# PCB-AC2b.net
KiCad netlist of a schematic drawn in EAGLE
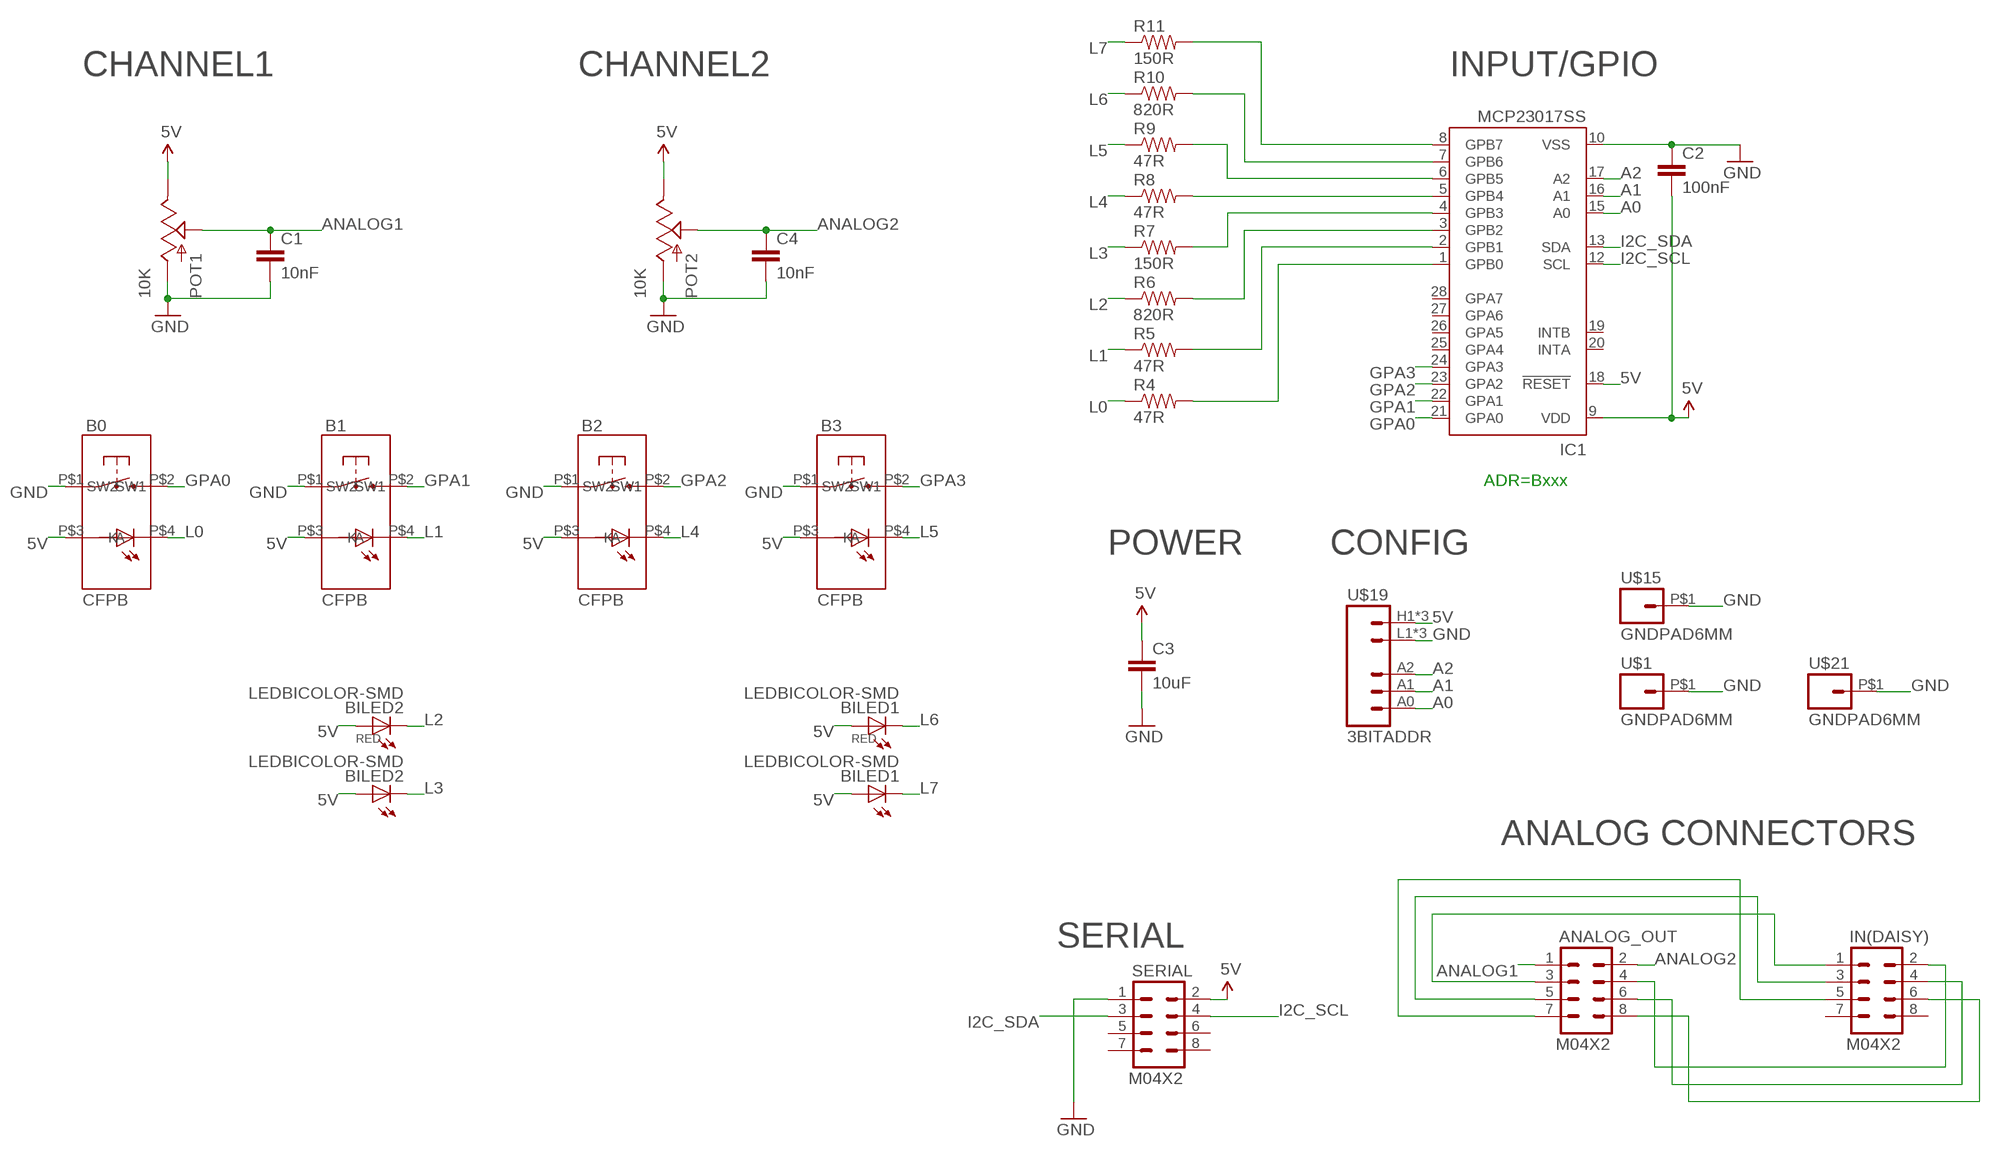
[diagram p0: schematic, sheet 1]

(export (version "E")
  (design (tool "Eeschema 10.0.6"))
  (components
    (comp (ref "ANALOG_OUT")
      (value "M04X2")
      (footprint "eagle-import:2X4")
      (libsource (lib "eagle-import") (part "M04X2"))
    )
    (comp (ref "B0")
      (value "CFPB")
      (footprint "eagle-import:CFPB-6_9MM")
      (libsource (lib "eagle-import") (part "CFPB"))
    )
    (comp (ref "B1")
      (value "CFPB")
      (footprint "eagle-import:CFPB-6_9MM")
      (libsource (lib "eagle-import") (part "CFPB"))
    )
    (comp (ref "B2")
      (value "CFPB")
      (footprint "eagle-import:CFPB-6_9MM")
      (libsource (lib "eagle-import") (part "CFPB"))
    )
    (comp (ref "B3")
      (value "CFPB")
      (footprint "eagle-import:CFPB-6_9MM")
      (libsource (lib "eagle-import") (part "CFPB"))
    )
    (comp (ref "BILED1")
      (value "LEDBICOLOR-SMD")
      (footprint "eagle-import:LEDBICOLOR-SMD")
      (libsource (lib "eagle-import") (part "LEDBICOLOR-SMD"))
    )
    (comp (ref "BILED2")
      (value "LEDBICOLOR-SMD")
      (footprint "eagle-import:LEDBICOLOR-SMD")
      (libsource (lib "eagle-import") (part "LEDBICOLOR-SMD"))
    )
    (comp (ref "C1")
      (value "10nF")
      (footprint "eagle-import:0603-CAP")
      (libsource (lib "eagle-import") (part "CAP0603-CAP"))
    )
    (comp (ref "C2")
      (value "100nF")
      (footprint "eagle-import:0603-CAP")
      (libsource (lib "eagle-import") (part "CAP0603-CAP"))
    )
    (comp (ref "C3")
      (value "10uF")
      (footprint "eagle-import:0805")
      (libsource (lib "eagle-import") (part "CAP0805"))
    )
    (comp (ref "C4")
      (value "10nF")
      (footprint "eagle-import:0603-CAP")
      (libsource (lib "eagle-import") (part "CAP0603-CAP"))
    )
    (comp (ref "IC1")
      (value "MCP23017SS")
      (footprint "eagle-import:SSOP28")
      (fields
        (field (name "MF") "MICROCHIP")
        (field (name "MPN") "MCP23017-E/SS")
        (field (name "MPN_1") "MCP23017-E/SS")
        (field (name "OC_FARNELL") "1467674")
        (field (name "OC_NEWARK") "31K2960")
      )
      (libsource (lib "eagle-import") (part "MCP23017SS"))
    )
    (comp (ref "IN(DAISY)")
      (value "M04X2")
      (footprint "eagle-import:2X4")
      (libsource (lib "eagle-import") (part "M04X2"))
    )
    (comp (ref "POT1")
      (value "10K")
      (footprint "eagle-import:ALPS_POT")
      (libsource (lib "eagle-import") (part "POT"))
    )
    (comp (ref "POT2")
      (value "10K")
      (footprint "eagle-import:ALPS_POT")
      (libsource (lib "eagle-import") (part "POT"))
    )
    (comp (ref "R4")
      (value "47R")
      (footprint "eagle-import:0603-RES")
      (libsource (lib "eagle-import") (part "RESISTOR0603-RES"))
    )
    (comp (ref "R5")
      (value "47R")
      (footprint "eagle-import:0603-RES")
      (libsource (lib "eagle-import") (part "RESISTOR0603-RES"))
    )
    (comp (ref "R6")
      (value "820R")
      (footprint "eagle-import:0603-RES")
      (libsource (lib "eagle-import") (part "RESISTOR0603-RES"))
    )
    (comp (ref "R7")
      (value "150R")
      (footprint "eagle-import:0603-RES")
      (libsource (lib "eagle-import") (part "RESISTOR0603-RES"))
    )
    (comp (ref "R8")
      (value "47R")
      (footprint "eagle-import:0603-RES")
      (libsource (lib "eagle-import") (part "RESISTOR0603-RES"))
    )
    (comp (ref "R9")
      (value "47R")
      (footprint "eagle-import:0603-RES")
      (libsource (lib "eagle-import") (part "RESISTOR0603-RES"))
    )
    (comp (ref "R10")
      (value "820R")
      (footprint "eagle-import:0603-RES")
      (libsource (lib "eagle-import") (part "RESISTOR0603-RES"))
    )
    (comp (ref "R11")
      (value "150R")
      (footprint "eagle-import:0603-RES")
      (libsource (lib "eagle-import") (part "RESISTOR0603-RES"))
    )
    (comp (ref "SERIAL")
      (value "M04X2")
      (footprint "eagle-import:2X4")
      (libsource (lib "eagle-import") (part "M04X2"))
    )
    (comp (ref "U$1")
      (value "GNDPAD6MM")
      (footprint "eagle-import:3.2MMPAD6MM")
      (libsource (lib "eagle-import") (part "GNDPAD6MM"))
    )
    (comp (ref "U$15")
      (value "GNDPAD6MM")
      (footprint "eagle-import:3.2MMPAD6MM")
      (libsource (lib "eagle-import") (part "GNDPAD6MM"))
    )
    (comp (ref "U$19")
      (value "3BITADDR")
      (footprint "eagle-import:3BITADDR")
      (libsource (lib "eagle-import") (part "3BITADDR"))
    )
    (comp (ref "U$21")
      (value "GNDPAD6MM")
      (footprint "eagle-import:3.2MMPAD6MM")
      (libsource (lib "eagle-import") (part "GNDPAD6MM"))
    )
  )
  (nets
    (net (code "1") (name "5V") (class "Default")
      (node (ref "B0") (pin "P$3") (pinfunction "A_P$3") (pintype "bidirectional"))
      (node (ref "B1") (pin "P$3") (pinfunction "A_P$3") (pintype "bidirectional"))
      (node (ref "B2") (pin "P$3") (pinfunction "A_P$3") (pintype "bidirectional"))
      (node (ref "B3") (pin "P$3") (pinfunction "A_P$3") (pintype "bidirectional"))
      (node (ref "BILED1") (pin "P$1") (pinfunction "A_P$1") (pintype "passive"))
      (node (ref "BILED1") (pin "P$3") (pinfunction "A1_P$3") (pintype "passive"))
      (node (ref "BILED2") (pin "P$1") (pinfunction "A_P$1") (pintype "passive"))
      (node (ref "BILED2") (pin "P$3") (pinfunction "A1_P$3") (pintype "passive"))
      (node (ref "C2") (pin "2") (pinfunction "2_2") (pintype "passive"))
      (node (ref "C3") (pin "1") (pinfunction "1_1") (pintype "passive"))
      (node (ref "IC1") (pin "18") (pinfunction "~{RESET}_18") (pintype "input"))
      (node (ref "IC1") (pin "9") (pinfunction "VDD_9") (pintype "power_in"))
      (node (ref "POT1") (pin "P$1") (pinfunction "E_P$1") (pintype "passive"))
      (node (ref "POT2") (pin "P$1") (pinfunction "E_P$1") (pintype "passive"))
      (node (ref "SERIAL") (pin "2") (pinfunction "2_2") (pintype "passive"))
      (node (ref "U$19") (pin "H1") (pinfunction "VCC_H1") (pintype "passive"))
      (node (ref "U$19") (pin "H2") (pinfunction "VCC_H2") (pintype "passive"))
      (node (ref "U$19") (pin "H3") (pinfunction "VCC_H3") (pintype "passive"))
    )
    (net (code "2") (name "A0") (class "Default")
      (node (ref "IC1") (pin "15") (pinfunction "A0_15") (pintype "input"))
      (node (ref "U$19") (pin "A0") (pinfunction "A0_A0") (pintype "passive"))
    )
    (net (code "3") (name "A1") (class "Default")
      (node (ref "IC1") (pin "16") (pinfunction "A1_16") (pintype "input"))
      (node (ref "U$19") (pin "A1") (pinfunction "A1_A1") (pintype "passive"))
    )
    (net (code "4") (name "A2") (class "Default")
      (node (ref "IC1") (pin "17") (pinfunction "A2_17") (pintype "input"))
      (node (ref "U$19") (pin "A2") (pinfunction "A2_A2") (pintype "passive"))
    )
    (net (code "5") (name "ANALOG1") (class "Default")
      (node (ref "ANALOG_OUT") (pin "1") (pinfunction "1_1") (pintype "passive"))
      (node (ref "C1") (pin "1") (pinfunction "1_1") (pintype "passive"))
      (node (ref "POT1") (pin "P$2") (pinfunction "S_P$2") (pintype "passive"))
    )
    (net (code "6") (name "ANALOG2") (class "Default")
      (node (ref "ANALOG_OUT") (pin "2") (pinfunction "2_2") (pintype "passive"))
      (node (ref "C4") (pin "1") (pinfunction "1_1") (pintype "passive"))
      (node (ref "POT2") (pin "P$2") (pinfunction "S_P$2") (pintype "passive"))
    )
    (net (code "7") (name "GND") (class "Default")
      (node (ref "B0") (pin "P$1") (pinfunction "SW1_P$1") (pintype "bidirectional"))
      (node (ref "B1") (pin "P$1") (pinfunction "SW1_P$1") (pintype "bidirectional"))
      (node (ref "B2") (pin "P$1") (pinfunction "SW1_P$1") (pintype "bidirectional"))
      (node (ref "B3") (pin "P$1") (pinfunction "SW1_P$1") (pintype "bidirectional"))
      (node (ref "C1") (pin "2") (pinfunction "2_2") (pintype "passive"))
      (node (ref "C2") (pin "1") (pinfunction "1_1") (pintype "passive"))
      (node (ref "C3") (pin "2") (pinfunction "2_2") (pintype "passive"))
      (node (ref "C4") (pin "2") (pinfunction "2_2") (pintype "passive"))
      (node (ref "IC1") (pin "10") (pinfunction "VSS_10") (pintype "power_in"))
      (node (ref "POT1") (pin "P$3") (pinfunction "A_P$3") (pintype "passive"))
      (node (ref "POT2") (pin "P$3") (pinfunction "A_P$3") (pintype "passive"))
      (node (ref "SERIAL") (pin "1") (pinfunction "1_1") (pintype "passive"))
      (node (ref "U$1") (pin "P$1") (pinfunction "1_P$1") (pintype "passive"))
      (node (ref "U$15") (pin "P$1") (pinfunction "1_P$1") (pintype "passive"))
      (node (ref "U$19") (pin "L1") (pinfunction "GND_L1") (pintype "passive"))
      (node (ref "U$19") (pin "L2") (pinfunction "GND_L2") (pintype "passive"))
      (node (ref "U$19") (pin "L3") (pinfunction "GND_L3") (pintype "passive"))
      (node (ref "U$21") (pin "P$1") (pinfunction "1_P$1") (pintype "passive"))
    )
    (net (code "8") (name "GPA0") (class "Default")
      (node (ref "B0") (pin "P$2") (pinfunction "SW2_P$2") (pintype "bidirectional"))
      (node (ref "IC1") (pin "21") (pinfunction "GPA0_21") (pintype "bidirectional"))
    )
    (net (code "9") (name "GPA1") (class "Default")
      (node (ref "B1") (pin "P$2") (pinfunction "SW2_P$2") (pintype "bidirectional"))
      (node (ref "IC1") (pin "22") (pinfunction "GPA1_22") (pintype "bidirectional"))
    )
    (net (code "10") (name "GPA2") (class "Default")
      (node (ref "B2") (pin "P$2") (pinfunction "SW2_P$2") (pintype "bidirectional"))
      (node (ref "IC1") (pin "23") (pinfunction "GPA2_23") (pintype "bidirectional"))
    )
    (net (code "11") (name "GPA3") (class "Default")
      (node (ref "B3") (pin "P$2") (pinfunction "SW2_P$2") (pintype "bidirectional"))
      (node (ref "IC1") (pin "24") (pinfunction "GPA3_24") (pintype "bidirectional"))
    )
    (net (code "12") (name "I2C_SCL") (class "Default")
      (node (ref "IC1") (pin "12") (pinfunction "SCL_12") (pintype "input"))
      (node (ref "SERIAL") (pin "4") (pinfunction "4_4") (pintype "passive"))
    )
    (net (code "13") (name "I2C_SDA") (class "Default")
      (node (ref "IC1") (pin "13") (pinfunction "SDA_13") (pintype "bidirectional"))
      (node (ref "SERIAL") (pin "3") (pinfunction "3_3") (pintype "passive"))
    )
    (net (code "14") (name "L0") (class "Default")
      (node (ref "B0") (pin "P$4") (pinfunction "K_P$4") (pintype "bidirectional"))
      (node (ref "R4") (pin "1") (pinfunction "1_1") (pintype "passive"))
    )
    (net (code "15") (name "L1") (class "Default")
      (node (ref "B1") (pin "P$4") (pinfunction "K_P$4") (pintype "bidirectional"))
      (node (ref "R5") (pin "1") (pinfunction "1_1") (pintype "passive"))
    )
    (net (code "16") (name "L2") (class "Default")
      (node (ref "BILED2") (pin "P$2") (pinfunction "C_P$2") (pintype "passive"))
      (node (ref "R6") (pin "1") (pinfunction "1_1") (pintype "passive"))
    )
    (net (code "17") (name "L3") (class "Default")
      (node (ref "BILED2") (pin "P$4") (pinfunction "C1_P$4") (pintype "passive"))
      (node (ref "R7") (pin "1") (pinfunction "1_1") (pintype "passive"))
    )
    (net (code "18") (name "L4") (class "Default")
      (node (ref "B2") (pin "P$4") (pinfunction "K_P$4") (pintype "bidirectional"))
      (node (ref "R8") (pin "1") (pinfunction "1_1") (pintype "passive"))
    )
    (net (code "19") (name "L5") (class "Default")
      (node (ref "B3") (pin "P$4") (pinfunction "K_P$4") (pintype "bidirectional"))
      (node (ref "R9") (pin "1") (pinfunction "1_1") (pintype "passive"))
    )
    (net (code "20") (name "L6") (class "Default")
      (node (ref "BILED1") (pin "P$2") (pinfunction "C_P$2") (pintype "passive"))
      (node (ref "R10") (pin "1") (pinfunction "1_1") (pintype "passive"))
    )
    (net (code "21") (name "L7") (class "Default")
      (node (ref "BILED1") (pin "P$4") (pinfunction "C1_P$4") (pintype "passive"))
      (node (ref "R11") (pin "1") (pinfunction "1_1") (pintype "passive"))
    )
    (net (code "22") (name "Net-(ANALOG_OUT-Pad3)") (class "Default")
      (node (ref "ANALOG_OUT") (pin "3") (pinfunction "3_3") (pintype "passive"))
      (node (ref "IN(DAISY)") (pin "1") (pinfunction "1_1") (pintype "passive"))
    )
    (net (code "23") (name "Net-(ANALOG_OUT-Pad4)") (class "Default")
      (node (ref "ANALOG_OUT") (pin "4") (pinfunction "4_4") (pintype "passive"))
      (node (ref "IN(DAISY)") (pin "2") (pinfunction "2_2") (pintype "passive"))
    )
    (net (code "24") (name "Net-(ANALOG_OUT-Pad5)") (class "Default")
      (node (ref "ANALOG_OUT") (pin "5") (pinfunction "5_5") (pintype "passive"))
      (node (ref "IN(DAISY)") (pin "3") (pinfunction "3_3") (pintype "passive"))
    )
    (net (code "25") (name "Net-(ANALOG_OUT-Pad6)") (class "Default")
      (node (ref "ANALOG_OUT") (pin "6") (pinfunction "6_6") (pintype "passive"))
      (node (ref "IN(DAISY)") (pin "4") (pinfunction "4_4") (pintype "passive"))
    )
    (net (code "26") (name "Net-(ANALOG_OUT-Pad7)") (class "Default")
      (node (ref "ANALOG_OUT") (pin "7") (pinfunction "7_7") (pintype "passive"))
      (node (ref "IN(DAISY)") (pin "5") (pinfunction "5_5") (pintype "passive"))
    )
    (net (code "27") (name "Net-(ANALOG_OUT-Pad8)") (class "Default")
      (node (ref "ANALOG_OUT") (pin "8") (pinfunction "8_8") (pintype "passive"))
      (node (ref "IN(DAISY)") (pin "6") (pinfunction "6_6") (pintype "passive"))
    )
    (net (code "28") (name "Net-(IC1-GPB0)") (class "Default")
      (node (ref "IC1") (pin "1") (pinfunction "GPB0_1") (pintype "bidirectional"))
      (node (ref "R4") (pin "2") (pinfunction "2_2") (pintype "passive"))
    )
    (net (code "29") (name "Net-(IC1-GPB1)") (class "Default")
      (node (ref "IC1") (pin "2") (pinfunction "GPB1_2") (pintype "bidirectional"))
      (node (ref "R5") (pin "2") (pinfunction "2_2") (pintype "passive"))
    )
    (net (code "30") (name "Net-(IC1-GPB2)") (class "Default")
      (node (ref "IC1") (pin "3") (pinfunction "GPB2_3") (pintype "bidirectional"))
      (node (ref "R6") (pin "2") (pinfunction "2_2") (pintype "passive"))
    )
    (net (code "31") (name "Net-(IC1-GPB3)") (class "Default")
      (node (ref "IC1") (pin "4") (pinfunction "GPB3_4") (pintype "bidirectional"))
      (node (ref "R7") (pin "2") (pinfunction "2_2") (pintype "passive"))
    )
    (net (code "32") (name "Net-(IC1-GPB4)") (class "Default")
      (node (ref "IC1") (pin "5") (pinfunction "GPB4_5") (pintype "bidirectional"))
      (node (ref "R8") (pin "2") (pinfunction "2_2") (pintype "passive"))
    )
    (net (code "33") (name "Net-(IC1-GPB5)") (class "Default")
      (node (ref "IC1") (pin "6") (pinfunction "GPB5_6") (pintype "bidirectional"))
      (node (ref "R9") (pin "2") (pinfunction "2_2") (pintype "passive"))
    )
    (net (code "34") (name "Net-(IC1-GPB6)") (class "Default")
      (node (ref "IC1") (pin "7") (pinfunction "GPB6_7") (pintype "bidirectional"))
      (node (ref "R10") (pin "2") (pinfunction "2_2") (pintype "passive"))
    )
    (net (code "35") (name "Net-(IC1-GPB7)") (class "Default")
      (node (ref "IC1") (pin "8") (pinfunction "GPB7_8") (pintype "bidirectional"))
      (node (ref "R11") (pin "2") (pinfunction "2_2") (pintype "passive"))
    )
    (net (code "36") (name "unconnected-(IC1-GPA4-Pad25)") (class "Default")
      (node (ref "IC1") (pin "25") (pinfunction "GPA4_25") (pintype "bidirectional"))
    )
    (net (code "37") (name "unconnected-(IC1-GPA5-Pad26)") (class "Default")
      (node (ref "IC1") (pin "26") (pinfunction "GPA5_26") (pintype "bidirectional"))
    )
    (net (code "38") (name "unconnected-(IC1-GPA6-Pad27)") (class "Default")
      (node (ref "IC1") (pin "27") (pinfunction "GPA6_27") (pintype "bidirectional"))
    )
    (net (code "39") (name "unconnected-(IC1-GPA7-Pad28)") (class "Default")
      (node (ref "IC1") (pin "28") (pinfunction "GPA7_28") (pintype "bidirectional"))
    )
    (net (code "40") (name "unconnected-(IC1-INTA-Pad20)") (class "Default")
      (node (ref "IC1") (pin "20") (pinfunction "INTA_20") (pintype "output"))
    )
    (net (code "41") (name "unconnected-(IC1-INTB-Pad19)") (class "Default")
      (node (ref "IC1") (pin "19") (pinfunction "INTB_19") (pintype "output"))
    )
    (net (code "42") (name "unconnected-(IN(DAISY)-Pad7)") (class "Default")
      (node (ref "IN(DAISY)") (pin "7") (pinfunction "7_7") (pintype "passive"))
    )
    (net (code "43") (name "unconnected-(IN(DAISY)-Pad8)") (class "Default")
      (node (ref "IN(DAISY)") (pin "8") (pinfunction "8_8") (pintype "passive"))
    )
    (net (code "44") (name "unconnected-(SERIAL-Pad5)") (class "Default")
      (node (ref "SERIAL") (pin "5") (pinfunction "5_5") (pintype "passive"))
    )
    (net (code "45") (name "unconnected-(SERIAL-Pad6)") (class "Default")
      (node (ref "SERIAL") (pin "6") (pinfunction "6_6") (pintype "passive"))
    )
    (net (code "46") (name "unconnected-(SERIAL-Pad7)") (class "Default")
      (node (ref "SERIAL") (pin "7") (pinfunction "7_7") (pintype "passive"))
    )
    (net (code "47") (name "unconnected-(SERIAL-Pad8)") (class "Default")
      (node (ref "SERIAL") (pin "8") (pinfunction "8_8") (pintype "passive"))
    )
  )
)
